# PowerSource.net
KiCad netlist of a schematic drawn in EAGLE
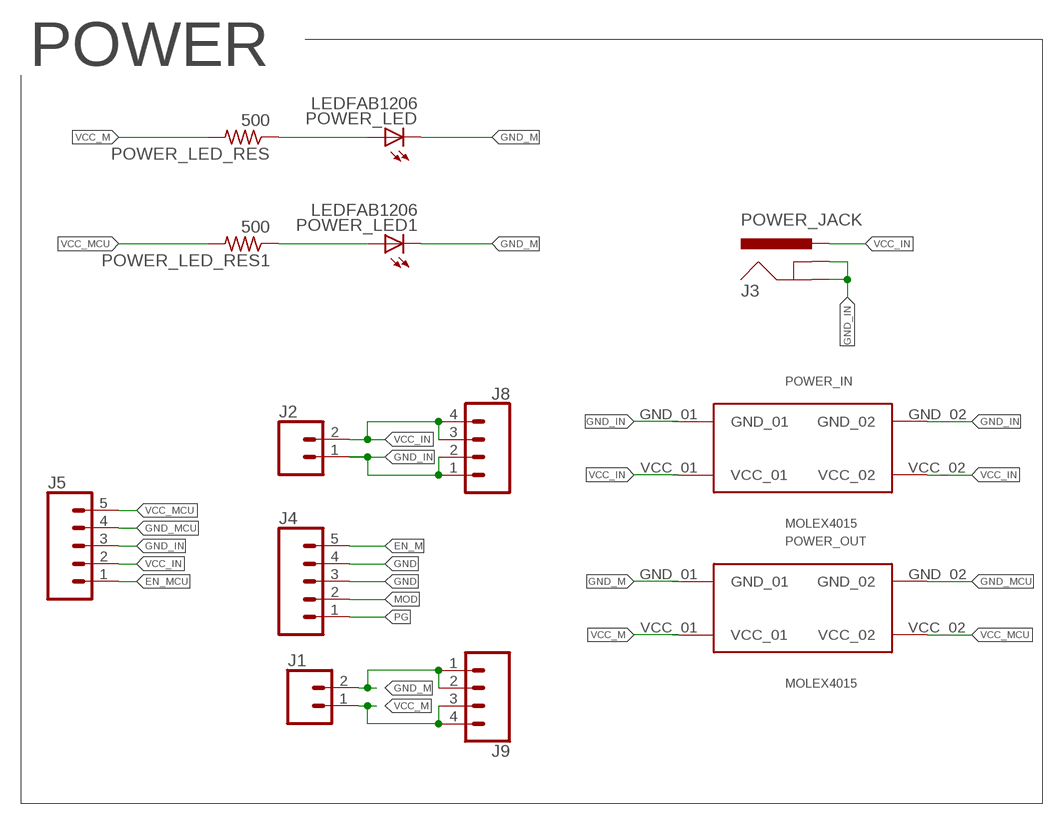
[diagram p0: schematic, sheet 1]

(export (version "E")
  (design (tool "Eeschema 10.0.6"))
  (components
    (comp (ref "J1")
      (value "CONN_02PTH4")
      (footprint "eagle-import:1X02_XTRA_BIG")
      (libsource (lib "eagle-import") (part "CONN_02PTH4"))
    )
    (comp (ref "J2")
      (value "CONN_02PTH4")
      (footprint "eagle-import:1X02_XTRA_BIG")
      (libsource (lib "eagle-import") (part "CONN_02PTH4"))
    )
    (comp (ref "J3")
      (value "POWER_JACK")
      (footprint "eagle-import:POWER_JACK_PTH")
      (libsource (lib "eagle-import") (part "POWER_JACK"))
    )
    (comp (ref "J4")
      (value "CONN_05NO_SILK")
      (footprint "eagle-import:1X05_NO_SILK")
      (libsource (lib "eagle-import") (part "CONN_05NO_SILK"))
    )
    (comp (ref "J5")
      (value "CONN_05NO_SILK")
      (footprint "eagle-import:1X05_NO_SILK")
      (libsource (lib "eagle-import") (part "CONN_05NO_SILK"))
    )
    (comp (ref "J8")
      (value "CONN_04")
      (footprint "eagle-import:1X04")
      (libsource (lib "eagle-import") (part "CONN_04"))
    )
    (comp (ref "J9")
      (value "CONN_04")
      (footprint "eagle-import:1X04")
      (libsource (lib "eagle-import") (part "CONN_04"))
    )
    (comp (ref "POWER_IN")
      (value "MOLEX4015")
      (footprint "eagle-import:MOLEX4015")
      (libsource (lib "eagle-import") (part "MOLEX4015"))
    )
    (comp (ref "POWER_LED")
      (value "LEDFAB1206")
      (footprint "eagle-import:LED1206FAB")
      (libsource (lib "eagle-import") (part "LEDFAB1206"))
    )
    (comp (ref "POWER_LED1")
      (value "LEDFAB1206")
      (footprint "eagle-import:LED1206FAB")
      (libsource (lib "eagle-import") (part "LEDFAB1206"))
    )
    (comp (ref "POWER_LED_RES")
      (value "500")
      (footprint "eagle-import:R1206FAB")
      (libsource (lib "eagle-import") (part "RES-US1206FAB"))
    )
    (comp (ref "POWER_LED_RES1")
      (value "500")
      (footprint "eagle-import:R1206FAB")
      (libsource (lib "eagle-import") (part "RES-US1206FAB"))
    )
    (comp (ref "POWER_OUT")
      (value "MOLEX4015")
      (footprint "eagle-import:MOLEX4015")
      (libsource (lib "eagle-import") (part "MOLEX4015"))
    )
  )
  (nets
    (net (code "1") (name "EN_M") (class "Default")
      (node (ref "J4") (pin "5") (pinfunction "5_5") (pintype "passive"))
    )
    (net (code "2") (name "EN_MCU") (class "Default")
      (node (ref "J5") (pin "1") (pinfunction "1_1") (pintype "passive"))
    )
    (net (code "3") (name "GND") (class "Default")
      (node (ref "J4") (pin "3") (pinfunction "3_3") (pintype "passive"))
      (node (ref "J4") (pin "4") (pinfunction "4_4") (pintype "passive"))
    )
    (net (code "4") (name "GND_IN") (class "Default")
      (node (ref "J2") (pin "1") (pinfunction "1_1") (pintype "passive"))
      (node (ref "J3") (pin "GND") (pinfunction "GND_GND") (pintype "bidirectional"))
      (node (ref "J3") (pin "GNDBREAK") (pinfunction "GNDBREAK_GNDBREAK") (pintype "bidirectional"))
      (node (ref "J5") (pin "3") (pinfunction "3_3") (pintype "passive"))
      (node (ref "J8") (pin "1") (pinfunction "1_1") (pintype "passive"))
      (node (ref "J8") (pin "2") (pinfunction "2_2") (pintype "passive"))
      (node (ref "POWER_IN") (pin "GND_01") (pinfunction "GND_01_GND_01") (pintype "bidirectional"))
      (node (ref "POWER_IN") (pin "GND_02") (pinfunction "GND_02_GND_02") (pintype "bidirectional"))
    )
    (net (code "5") (name "GND_M") (class "Default")
      (node (ref "J1") (pin "2") (pinfunction "2_2") (pintype "passive"))
      (node (ref "J9") (pin "1") (pinfunction "1_1") (pintype "passive"))
      (node (ref "J9") (pin "2") (pinfunction "2_2") (pintype "passive"))
      (node (ref "POWER_LED") (pin "2") (pinfunction "C_2") (pintype "passive"))
      (node (ref "POWER_LED1") (pin "2") (pinfunction "C_2") (pintype "passive"))
      (node (ref "POWER_OUT") (pin "GND_01") (pinfunction "GND_01_GND_01") (pintype "bidirectional"))
    )
    (net (code "6") (name "GND_MCU") (class "Default")
      (node (ref "J5") (pin "4") (pinfunction "4_4") (pintype "passive"))
      (node (ref "POWER_OUT") (pin "GND_02") (pinfunction "GND_02_GND_02") (pintype "bidirectional"))
    )
    (net (code "7") (name "MOD") (class "Default")
      (node (ref "J4") (pin "2") (pinfunction "2_2") (pintype "passive"))
    )
    (net (code "8") (name "Net-(POWER_LED-A)") (class "Default")
      (node (ref "POWER_LED") (pin "1") (pinfunction "A_1") (pintype "passive"))
      (node (ref "POWER_LED_RES") (pin "1") (pinfunction "1_1") (pintype "passive"))
    )
    (net (code "9") (name "Net-(POWER_LED1-A)") (class "Default")
      (node (ref "POWER_LED1") (pin "1") (pinfunction "A_1") (pintype "passive"))
      (node (ref "POWER_LED_RES1") (pin "1") (pinfunction "1_1") (pintype "passive"))
    )
    (net (code "10") (name "PG") (class "Default")
      (node (ref "J4") (pin "1") (pinfunction "1_1") (pintype "passive"))
    )
    (net (code "11") (name "VCC_IN") (class "Default")
      (node (ref "J2") (pin "2") (pinfunction "2_2") (pintype "passive"))
      (node (ref "J3") (pin "PWR") (pinfunction "PWR_PWR") (pintype "bidirectional"))
      (node (ref "J5") (pin "2") (pinfunction "2_2") (pintype "passive"))
      (node (ref "J8") (pin "3") (pinfunction "3_3") (pintype "passive"))
      (node (ref "J8") (pin "4") (pinfunction "4_4") (pintype "passive"))
      (node (ref "POWER_IN") (pin "VCC_01") (pinfunction "VCC_01_VCC_01") (pintype "bidirectional"))
      (node (ref "POWER_IN") (pin "VCC_02") (pinfunction "VCC_02_VCC_02") (pintype "bidirectional"))
    )
    (net (code "12") (name "VCC_M") (class "Default")
      (node (ref "J1") (pin "1") (pinfunction "1_1") (pintype "passive"))
      (node (ref "J9") (pin "3") (pinfunction "3_3") (pintype "passive"))
      (node (ref "J9") (pin "4") (pinfunction "4_4") (pintype "passive"))
      (node (ref "POWER_LED_RES") (pin "2") (pinfunction "2_2") (pintype "passive"))
      (node (ref "POWER_OUT") (pin "VCC_01") (pinfunction "VCC_01_VCC_01") (pintype "bidirectional"))
    )
    (net (code "13") (name "VCC_MCU") (class "Default")
      (node (ref "J5") (pin "5") (pinfunction "5_5") (pintype "passive"))
      (node (ref "POWER_LED_RES1") (pin "2") (pinfunction "2_2") (pintype "passive"))
      (node (ref "POWER_OUT") (pin "VCC_02") (pinfunction "VCC_02_VCC_02") (pintype "bidirectional"))
    )
  )
)
